# eBox_Power.net
KiCad netlist of a schematic drawn in Altium Designer
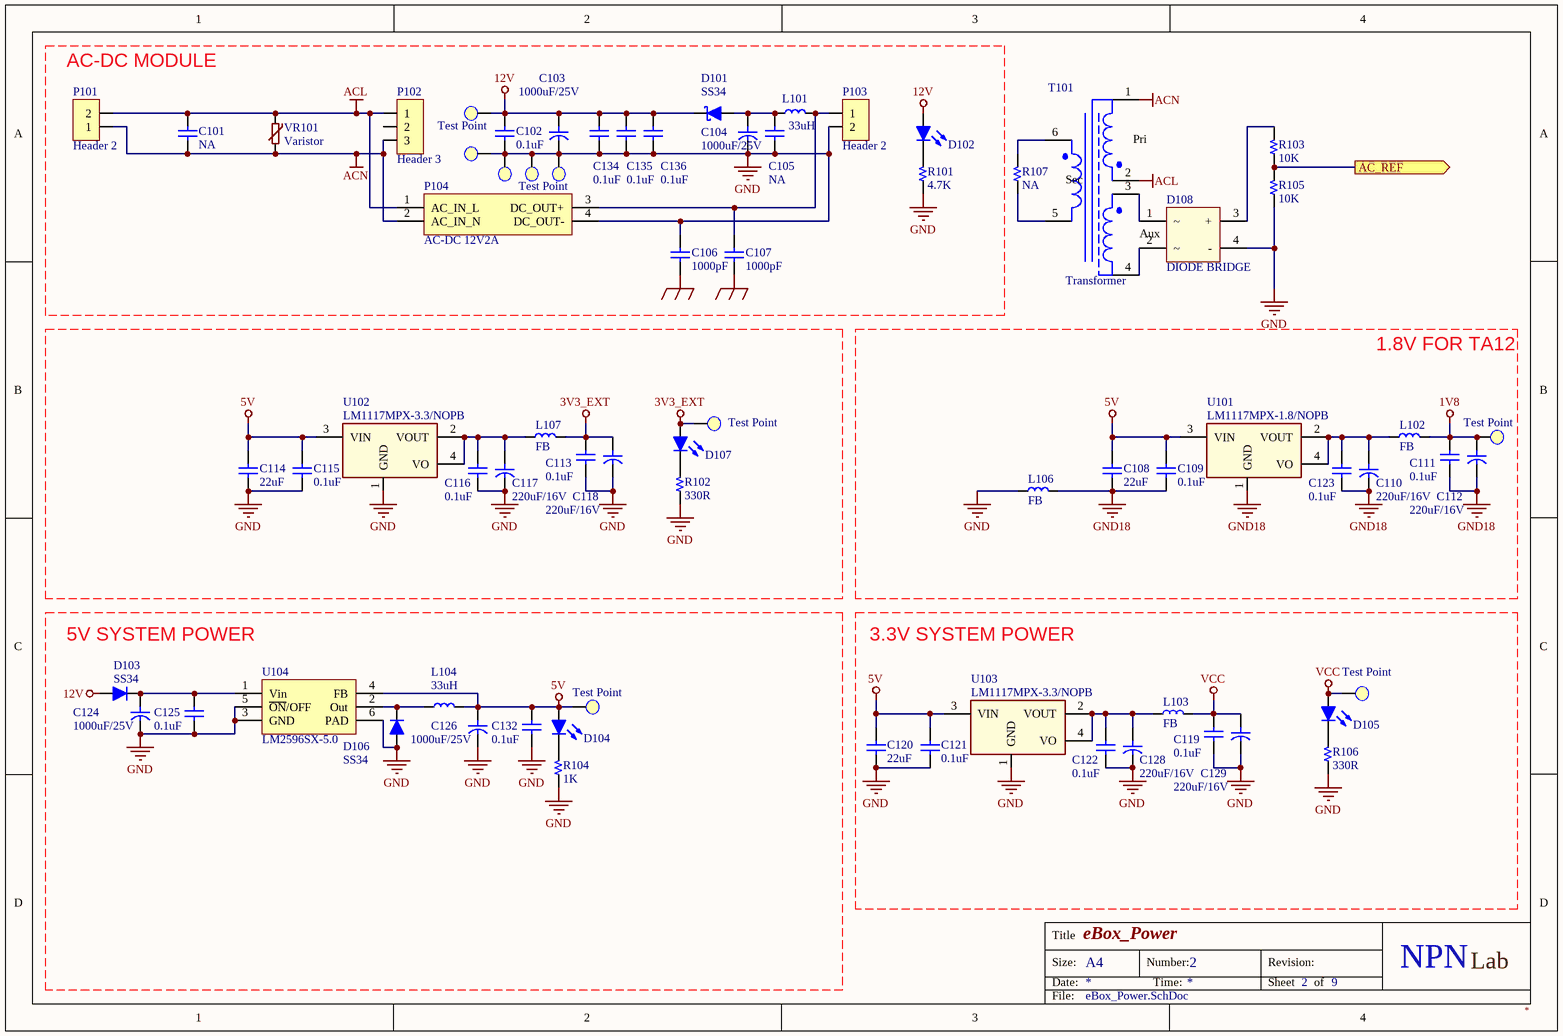
[diagram p0: eBox_Power.SchDoc]

(export (version "E")
  (design (tool "Eeschema 10.0.6"))
  (components
    (comp (ref "1V8")
      (value "Test Point")
      (footprint "TestPoint/SMD/1.5mm")
      (libsource (lib "chipfc_altium_libs_extras") (part "Test Point"))
    )
    (comp (ref "3V3")
      (value "Test Point")
      (footprint "TestPoint/SMD/1.5mm")
      (libsource (lib "chipfc_altium_libs_extras") (part "Test Point"))
    )
    (comp (ref "5V")
      (value "Test Point")
      (footprint "TestPoint/SMD/1.5mm")
      (libsource (lib "chipfc_altium_libs_extras") (part "Test Point"))
    )
    (comp (ref "12V")
      (value "Test Point")
      (footprint "TestPoint/SMD/1.5mm")
      (libsource (lib "chipfc_altium_libs_extras") (part "Test Point"))
    )
    (comp (ref "C101")
      (value "NA")
      (footprint "CAP Ceramic/D7.0/F7.5")
      (description "Capacitor non-pol")
      (libsource (lib "chipfc_altium_libs") (part "Capacitor NP"))
    )
    (comp (ref "C102")
      (value "0.1uF")
      (footprint "C 0805")
      (description "CAP CER 0.1UF 50V X7R 0805")
      (libsource (lib "chipfc_altium_libs") (part "Capacitor NP"))
    )
    (comp (ref "C103")
      (value "1000uF/25V")
      (footprint "CAP/D100/H200/LS50")
      (description "CAP ALUM 1000UF 20% 25V RADIAL")
      (libsource (lib "") (part "Capacitor_1"))
    )
    (comp (ref "C104")
      (value "1000uF/25V")
      (footprint "CAP/D100/H200/LS50")
      (description "CAP ALUM 1000UF 20% 25V RADIAL")
      (libsource (lib "") (part "Capacitor_1"))
    )
    (comp (ref "C105")
      (value "NA")
      (footprint "C 0805")
      (description "CAP SMD 0805")
      (libsource (lib "chipfc_altium_libs") (part "Capacitor NP"))
    )
    (comp (ref "C106")
      (value "1000pF")
      (footprint "CAP Ceramic/W300")
      (description "Capacitor non-pol")
      (libsource (lib "chipfc_altium_libs") (part "Capacitor NP"))
    )
    (comp (ref "C107")
      (value "1000pF")
      (footprint "CAP Ceramic/W300")
      (description "Capacitor non-pol")
      (libsource (lib "chipfc_altium_libs") (part "Capacitor NP"))
    )
    (comp (ref "C108")
      (value "22uF")
      (footprint "C 1210")
      (description "CAP CER 22UF 50V X7R 1210")
      (libsource (lib "chipfc_altium_libs") (part "Capacitor NP"))
    )
    (comp (ref "C109")
      (value "0.1uF")
      (footprint "C 0805")
      (description "CAP CER 0.1UF 50V X7R 0805")
      (libsource (lib "chipfc_altium_libs") (part "Capacitor NP"))
    )
    (comp (ref "C110")
      (value "220uF/16V")
      (footprint "CYL/D.250/LS.100")
      (description "CAP ALUM 220UF 20% 16V RADIAL")
      (libsource (lib "chipfc_altium_libs") (part "Capacitor"))
    )
    (comp (ref "C111")
      (value "0.1uF")
      (footprint "C 0805")
      (description "CAP CER 0.1UF 50V X7R 0805")
      (libsource (lib "chipfc_altium_libs") (part "Capacitor NP"))
    )
    (comp (ref "C112")
      (value "220uF/16V")
      (footprint "CYL/D.250/LS.100")
      (description "CAP ALUM 220UF 20% 16V RADIAL")
      (libsource (lib "chipfc_altium_libs") (part "Capacitor"))
    )
    (comp (ref "C113")
      (value "0.1uF")
      (footprint "C 0805")
      (description "CAP CER 0.1UF 50V X7R 0805")
      (libsource (lib "chipfc_altium_libs") (part "Capacitor NP"))
    )
    (comp (ref "C114")
      (value "22uF")
      (footprint "C 1210")
      (description "CAP CER 22UF 50V X7R 1210")
      (libsource (lib "chipfc_altium_libs") (part "Capacitor NP"))
    )
    (comp (ref "C115")
      (value "0.1uF")
      (footprint "C 0805")
      (description "CAP CER 0.1UF 50V X7R 0805")
      (libsource (lib "chipfc_altium_libs") (part "Capacitor NP"))
    )
    (comp (ref "C116")
      (value "0.1uF")
      (footprint "C 0805")
      (description "CAP CER 0.1UF 50V X7R 0805")
      (libsource (lib "chipfc_altium_libs") (part "Capacitor NP"))
    )
    (comp (ref "C117")
      (value "220uF/16V")
      (footprint "CYL/D.250/LS.100")
      (description "CAP ALUM 220UF 20% 16V RADIAL")
      (libsource (lib "chipfc_altium_libs") (part "Capacitor"))
    )
    (comp (ref "C118")
      (value "220uF/16V")
      (footprint "CYL/D.250/LS.100")
      (description "CAP ALUM 220UF 20% 16V RADIAL")
      (libsource (lib "chipfc_altium_libs") (part "Capacitor"))
    )
    (comp (ref "C119")
      (value "0.1uF")
      (footprint "C 0805")
      (description "CAP CER 0.1UF 50V X7R 0805")
      (libsource (lib "chipfc_altium_libs") (part "Capacitor NP"))
    )
    (comp (ref "C120")
      (value "22uF")
      (footprint "C 1210")
      (description "CAP CER 22UF 50V X7R 1210")
      (libsource (lib "chipfc_altium_libs") (part "Capacitor NP"))
    )
    (comp (ref "C121")
      (value "0.1uF")
      (footprint "C 0805")
      (description "CAP CER 0.1UF 50V X7R 0805")
      (libsource (lib "chipfc_altium_libs") (part "Capacitor NP"))
    )
    (comp (ref "C122")
      (value "0.1uF")
      (footprint "C 0805")
      (description "CAP CER 0.1UF 50V X7R 0805")
      (libsource (lib "chipfc_altium_libs") (part "Capacitor NP"))
    )
    (comp (ref "C123")
      (value "0.1uF")
      (footprint "C 0805")
      (description "CAP CER 0.1UF 50V X7R 0805")
      (libsource (lib "chipfc_altium_libs") (part "Capacitor NP"))
    )
    (comp (ref "C124")
      (value "1000uF/25V")
      (footprint "CAP/D100/H200/LS50")
      (description "CAP ALUM 1000UF 20% 25V RADIAL")
      (libsource (lib "") (part "Capacitor_1"))
    )
    (comp (ref "C125")
      (value "0.1uF")
      (footprint "C 0805")
      (description "CAP CER 0.1UF 50V X7R 0805")
      (libsource (lib "chipfc_altium_libs") (part "Capacitor NP"))
    )
    (comp (ref "C126")
      (value "1000uF/25V")
      (footprint "CAP/D100/H200/LS50")
      (description "CAP ALUM 1000UF 20% 25V RADIAL")
      (libsource (lib "") (part "Capacitor_1"))
    )
    (comp (ref "C128")
      (value "220uF/16V")
      (footprint "CYL/D.250/LS.100")
      (description "CAP ALUM 220UF 20% 16V RADIAL")
      (libsource (lib "chipfc_altium_libs") (part "Capacitor"))
    )
    (comp (ref "C129")
      (value "220uF/16V")
      (footprint "CYL/D.250/LS.100")
      (description "CAP ALUM 220UF 20% 16V RADIAL")
      (libsource (lib "chipfc_altium_libs") (part "Capacitor"))
    )
    (comp (ref "C132")
      (value "0.1uF")
      (footprint "C 0805")
      (description "CAP CER 0.1UF 50V X7R 0805")
      (libsource (lib "chipfc_altium_libs") (part "Capacitor NP"))
    )
    (comp (ref "C134")
      (value "0.1uF")
      (footprint "C 0805")
      (description "CAP CER 0.1UF 50V X7R 0805")
      (libsource (lib "chipfc_altium_libs") (part "Capacitor NP"))
    )
    (comp (ref "C135")
      (value "0.1uF")
      (footprint "C 0805")
      (description "CAP CER 0.1UF 50V X7R 0805")
      (libsource (lib "chipfc_altium_libs") (part "Capacitor NP"))
    )
    (comp (ref "C136")
      (value "0.1uF")
      (footprint "C 0805")
      (description "CAP CER 0.1UF 50V X7R 0805")
      (libsource (lib "chipfc_altium_libs") (part "Capacitor NP"))
    )
    (comp (ref "D101")
      (value "SS34")
      (footprint "DO-214AB (SMC)")
      (description "DIODE SCHOTTKY 40V 3A SUB SMA")
      (libsource (lib "chipfc_altium_libs") (part "Diode Schottky"))
    )
    (comp (ref "D102")
      (value "LED RED 3MM")
      (footprint "LED 3MM - red")
      (description "LED RED CLEAR 0603 SMD")
      (libsource (lib "chipfc_altium_libs") (part "Led"))
    )
    (comp (ref "D103")
      (value "SS34")
      (footprint "DO-214AC (SMA) L")
      (description "DIODE SCHOTTKY 40V 3A SUB SMA")
      (libsource (lib "chipfc_altium_libs") (part "Diode"))
    )
    (comp (ref "D104")
      (value "LED RED 3MM")
      (footprint "LED 3MM - red")
      (description "LED RED CLEAR 0603 SMD")
      (libsource (lib "chipfc_altium_libs") (part "Led"))
    )
    (comp (ref "D105")
      (value "LED RED 3MM")
      (footprint "LED 3MM - red")
      (description "LED RED CLEAR 0603 SMD")
      (libsource (lib "chipfc_altium_libs") (part "Led"))
    )
    (comp (ref "D106")
      (value "SS34")
      (footprint "DO-214AC (SMA) L")
      (description "DIODE SCHOTTKY 40V 3A SUB SMA")
      (libsource (lib "chipfc_altium_libs") (part "Diode"))
    )
    (comp (ref "D107")
      (value "LED RED 3MM")
      (footprint "LED 3MM - red")
      (description "LED RED CLEAR 0603 SMD")
      (libsource (lib "chipfc_altium_libs") (part "Led"))
    )
    (comp (ref "D108")
      (value "DIODE BRIDGE")
      (footprint "DiodeBridge-SOIC4")
      (description "BRIDGE RECT 1P 600V 500MA 4SOIC")
      (libsource (lib "chipfc_altium_libs") (part "DIODE BRIDGE"))
    )
    (comp (ref "GND1")
      (value "Test Point")
      (footprint "TESTPOINT/1/Black")
      (libsource (lib "chipfc_altium_libs_extras") (part "Test Point"))
    )
    (comp (ref "GND2")
      (value "Test Point")
      (footprint "TESTPOINT/1/Black")
      (libsource (lib "chipfc_altium_libs_extras") (part "Test Point"))
    )
    (comp (ref "GND3")
      (value "Test Point")
      (footprint "TESTPOINT/1/Black")
      (libsource (lib "chipfc_altium_libs_extras") (part "Test Point"))
    )
    (comp (ref "GND4")
      (value "Test Point")
      (footprint "TESTPOINT/1/Black")
      (libsource (lib "chipfc_altium_libs_extras") (part "Test Point"))
    )
    (comp (ref "L101")
      (value "33uH")
      (footprint "Inductor SMD 6.5x6.5x3.0")
      (description "FIXED IND 33UH 3A 105 MOHM SMD")
      (fields (field (name "PART NO") "MHCI06030-2R2M-R8"))
      (libsource (lib "chipfc_altium_libs") (part "Inductor"))
    )
    (comp (ref "L102")
      (value "FB")
      (footprint "L 0805 (2012)")
      (description "Chip Ferrite Bead")
      (libsource (lib "chipfc_altium_libs") (part "Inductor"))
    )
    (comp (ref "L103")
      (value "FB")
      (footprint "L 0805 (2012)")
      (description "Chip Ferrite Bead")
      (libsource (lib "chipfc_altium_libs") (part "Inductor"))
    )
    (comp (ref "L104")
      (value "33uH")
      (footprint "Inductor SMD 12x12x8")
      (description "FIXED IND 33UH 3A 64.8 MOHM SMD")
      (libsource (lib "chipfc_altium_libs") (part "Inductor"))
    )
    (comp (ref "L105")
      (value "33uH")
      (footprint "Inductor SMD 12x12x8")
      (description "FIXED IND 33UH 3A 64.8 MOHM SMD")
      (libsource (lib "chipfc_altium_libs") (part "Inductor"))
    )
    (comp (ref "L106")
      (value "FB")
      (footprint "L 0805 (2012)")
      (description "Chip Ferrite Bead")
      (libsource (lib "chipfc_altium_libs") (part "Inductor"))
    )
    (comp (ref "L107")
      (value "FB")
      (footprint "L 0805 (2012)")
      (description "Chip Ferrite Bead")
      (libsource (lib "chipfc_altium_libs") (part "Inductor"))
    )
    (comp (ref "P101")
      (value "Header 2")
      (footprint "HDR/Terminal/2/10mm")
      (description "Header, 2-Pin")
      (libsource (lib "chipfc_altium_libs") (part "Header 2"))
    )
    (comp (ref "P102")
      (value "Header 3")
      (footprint "HDR/Header/3/VH")
      (description "Header, 3-Pin")
      (libsource (lib "chipfc_altium_libs") (part "Header 3"))
    )
    (comp (ref "P103")
      (value "Header 2")
      (footprint "HDR/Header/2/VH")
      (description "Header, 2-Pin")
      (libsource (lib "") (part "Header 2_1"))
    )
    (comp (ref "P104")
      (value "AC-DC 12V2A")
      (footprint "AC-DC 12V2A")
      (description "AC-DC 12V2A MODULE")
      (libsource (lib "chipfc_altium_libs") (part "AC-DC 12V3A"))
    )
    (comp (ref "R101")
      (value "4.7K")
      (footprint "R 0603")
      (description "RES SMD 4.7K OHM 1% 1/10W 0603")
      (libsource (lib "chipfc_altium_libs") (part "Resistor"))
    )
    (comp (ref "R102")
      (value "330R")
      (footprint "R 0603")
      (description "RES SMD 330 OHM 1% 1/10W 0603")
      (libsource (lib "chipfc_altium_libs") (part "Resistor"))
    )
    (comp (ref "R103")
      (value "10K")
      (footprint "R 0805")
      (description "RES SMD 10K OHM 1% 1/10W 0603")
      (libsource (lib "chipfc_altium_libs") (part "Resistor"))
    )
    (comp (ref "R104")
      (value "1K")
      (footprint "R 0603")
      (description "RES SMD 1K OHM 1% 1/10W 0603")
      (libsource (lib "chipfc_altium_libs") (part "Resistor"))
    )
    (comp (ref "R105")
      (value "10K")
      (footprint "R 0805")
      (description "RES SMD 10K OHM 1% 1/10W 0603")
      (libsource (lib "chipfc_altium_libs") (part "Resistor"))
    )
    (comp (ref "R106")
      (value "330R")
      (footprint "R 0603")
      (description "RES SMD 330 OHM 1% 1/10W 0603")
      (libsource (lib "chipfc_altium_libs") (part "Resistor"))
    )
    (comp (ref "R107")
      (value "NA")
      (footprint "R 0805")
      (description "RES SMD 0805")
      (libsource (lib "chipfc_altium_libs") (part "Resistor"))
    )
    (comp (ref "T101")
      (value "Transformer")
      (footprint "Trans. EE10/6P/F")
      (description "Transformer 6-PIN")
      (libsource (lib "chipfc_altium_libs") (part "Trans 6-PIN"))
    )
    (comp (ref "U101")
      (value "LM1117MPX-1.8/NOPB")
      (footprint "SOT-223")
      (description "IC REG LINEAR 1.8V 800MA SOT223")
      (libsource (lib "chipfc_altium_libs") (part "AMS1117"))
    )
    (comp (ref "U102")
      (value "LM1117MPX-3.3/NOPB")
      (footprint "SOT-223")
      (description "IC REG LINEAR 3.3V 800MA SOT223")
      (libsource (lib "chipfc_altium_libs") (part "AMS1117"))
    )
    (comp (ref "U103")
      (value "LM1117MPX-3.3/NOPB")
      (footprint "SOT-223")
      (description "IC REG LINEAR 3.3V 800MA SOT223")
      (libsource (lib "chipfc_altium_libs") (part "AMS1117"))
    )
    (comp (ref "U104")
      (value "LM2596SX-5.0")
      (footprint "TO-263-6")
      (description "IC REG BUCK 5V 3A TO263-5")
      (fields (field (name "PART NO") "LM2576SX-5.0/NOPB"))
      (libsource (lib "chipfc_altium_libs") (part "LM2576SX-5.0"))
    )
    (comp (ref "VCC")
      (value "Test Point")
      (footprint "TestPoint/SMD/1.5mm")
      (libsource (lib "chipfc_altium_libs_extras") (part "Test Point"))
    )
    (comp (ref "VR101")
      (value "Varistor")
      (footprint "VARISTOR DISC 5MM/7MM")
      (libsource (lib "chipfc_altium_libs") (part "Varistor"))
    )
  )
  (nets
    (net (code "1") (name "/AC_REF") (class "Default")
      (node (ref "R103") (pin "1") (pinfunction "1_1") (pintype "passive"))
      (node (ref "R105") (pin "2") (pinfunction "2_2") (pintype "passive"))
    )
    (net (code "2") (name "1V8") (class "Default")
      (node (ref "1V8") (pin "1") (pinfunction "TP_1") (pintype "passive"))
      (node (ref "C111") (pin "1") (pinfunction "1_1") (pintype "passive"))
      (node (ref "C112") (pin "1") (pinfunction "1_1") (pintype "passive"))
      (node (ref "L102") (pin "2") (pinfunction "2_2") (pintype "passive"))
    )
    (net (code "3") (name "3V3_EXT") (class "Default")
      (node (ref "3V3") (pin "1") (pinfunction "TP_1") (pintype "passive"))
      (node (ref "C113") (pin "1") (pinfunction "1_1") (pintype "passive"))
      (node (ref "C118") (pin "1") (pinfunction "1_1") (pintype "passive"))
      (node (ref "D107") (pin "1") (pinfunction "A_1") (pintype "passive"))
      (node (ref "L107") (pin "2") (pinfunction "2_2") (pintype "passive"))
    )
    (net (code "4") (name "5V") (class "Default")
      (node (ref "5V") (pin "1") (pinfunction "TP_1") (pintype "passive"))
      (node (ref "C108") (pin "1") (pinfunction "1_1") (pintype "passive"))
      (node (ref "C109") (pin "1") (pinfunction "1_1") (pintype "passive"))
      (node (ref "C114") (pin "1") (pinfunction "1_1") (pintype "passive"))
      (node (ref "C115") (pin "1") (pinfunction "1_1") (pintype "passive"))
      (node (ref "C120") (pin "1") (pinfunction "1_1") (pintype "passive"))
      (node (ref "C121") (pin "1") (pinfunction "1_1") (pintype "passive"))
      (node (ref "C126") (pin "1") (pinfunction "1_1") (pintype "passive"))
      (node (ref "C132") (pin "1") (pinfunction "1_1") (pintype "passive"))
      (node (ref "D104") (pin "1") (pinfunction "A_1") (pintype "passive"))
      (node (ref "L104") (pin "2") (pinfunction "2_2") (pintype "passive"))
      (node (ref "U101") (pin "3") (pinfunction "VIN_3") (pintype "power_in"))
      (node (ref "U102") (pin "3") (pinfunction "VIN_3") (pintype "power_in"))
      (node (ref "U103") (pin "3") (pinfunction "VIN_3") (pintype "power_in"))
      (node (ref "U104") (pin "4") (pinfunction "FB_4") (pintype "passive"))
    )
    (net (code "5") (name "12V") (class "Default")
      (node (ref "12V") (pin "1") (pinfunction "TP_1") (pintype "passive"))
      (node (ref "C102") (pin "1") (pinfunction "1_1") (pintype "passive"))
      (node (ref "C103") (pin "1") (pinfunction "1_1") (pintype "passive"))
      (node (ref "C134") (pin "1") (pinfunction "1_1") (pintype "passive"))
      (node (ref "C135") (pin "1") (pinfunction "1_1") (pintype "passive"))
      (node (ref "C136") (pin "1") (pinfunction "1_1") (pintype "passive"))
      (node (ref "D101") (pin "2") (pinfunction "K_2") (pintype "passive"))
      (node (ref "D102") (pin "1") (pinfunction "A_1") (pintype "passive"))
      (node (ref "D103") (pin "1") (pinfunction "A_1") (pintype "passive"))
    )
    (net (code "6") (name "ACL") (class "Default")
      (node (ref "C101") (pin "1") (pinfunction "1_1") (pintype "passive"))
      (node (ref "P101") (pin "2") (pinfunction "2_2") (pintype "passive"))
      (node (ref "P102") (pin "1") (pinfunction "1_1") (pintype "passive"))
      (node (ref "P104") (pin "1") (pinfunction "AC_IN_L_1") (pintype "passive"))
      (node (ref "T101") (pin "2") (pinfunction "A2_2") (pintype "passive"))
      (node (ref "VR101") (pin "2") (pinfunction "2_2") (pintype "passive"))
    )
    (net (code "7") (name "ACN") (class "Default")
      (node (ref "C101") (pin "2") (pinfunction "2_2") (pintype "passive"))
      (node (ref "P101") (pin "1") (pinfunction "1_1") (pintype "passive"))
      (node (ref "P102") (pin "3") (pinfunction "3_3") (pintype "passive"))
      (node (ref "P104") (pin "2") (pinfunction "AC_IN_N_2") (pintype "passive"))
      (node (ref "T101") (pin "1") (pinfunction "A1_1") (pintype "passive"))
      (node (ref "VR101") (pin "1") (pinfunction "1_1") (pintype "passive"))
    )
    (net (code "8") (name "GND") (class "Default")
      (node (ref "C102") (pin "2") (pinfunction "2_2") (pintype "passive"))
      (node (ref "C103") (pin "2") (pinfunction "2_2") (pintype "passive"))
      (node (ref "C104") (pin "2") (pinfunction "2_2") (pintype "passive"))
      (node (ref "C105") (pin "2") (pinfunction "2_2") (pintype "passive"))
      (node (ref "C106") (pin "1") (pinfunction "1_1") (pintype "passive"))
      (node (ref "C113") (pin "2") (pinfunction "2_2") (pintype "passive"))
      (node (ref "C114") (pin "2") (pinfunction "2_2") (pintype "passive"))
      (node (ref "C115") (pin "2") (pinfunction "2_2") (pintype "passive"))
      (node (ref "C116") (pin "2") (pinfunction "2_2") (pintype "passive"))
      (node (ref "C117") (pin "2") (pinfunction "2_2") (pintype "passive"))
      (node (ref "C118") (pin "2") (pinfunction "2_2") (pintype "passive"))
      (node (ref "C119") (pin "2") (pinfunction "2_2") (pintype "passive"))
      (node (ref "C120") (pin "2") (pinfunction "2_2") (pintype "passive"))
      (node (ref "C121") (pin "2") (pinfunction "2_2") (pintype "passive"))
      (node (ref "C122") (pin "2") (pinfunction "2_2") (pintype "passive"))
      (node (ref "C124") (pin "2") (pinfunction "2_2") (pintype "passive"))
      (node (ref "C125") (pin "2") (pinfunction "2_2") (pintype "passive"))
      (node (ref "C126") (pin "2") (pinfunction "2_2") (pintype "passive"))
      (node (ref "C128") (pin "2") (pinfunction "2_2") (pintype "passive"))
      (node (ref "C129") (pin "2") (pinfunction "2_2") (pintype "passive"))
      (node (ref "C132") (pin "2") (pinfunction "2_2") (pintype "passive"))
      (node (ref "C134") (pin "2") (pinfunction "2_2") (pintype "passive"))
      (node (ref "C135") (pin "2") (pinfunction "2_2") (pintype "passive"))
      (node (ref "C136") (pin "2") (pinfunction "2_2") (pintype "passive"))
      (node (ref "D106") (pin "1") (pinfunction "A_1") (pintype "passive"))
      (node (ref "D108") (pin "4") (pinfunction "-_4") (pintype "passive"))
      (node (ref "GND1") (pin "1") (pinfunction "TP_1") (pintype "passive"))
      (node (ref "GND2") (pin "1") (pinfunction "TP_1") (pintype "passive"))
      (node (ref "GND3") (pin "1") (pinfunction "TP_1") (pintype "passive"))
      (node (ref "GND4") (pin "1") (pinfunction "TP_1") (pintype "passive"))
      (node (ref "L106") (pin "1") (pinfunction "1_1") (pintype "passive"))
      (node (ref "P103") (pin "2") (pinfunction "2_2") (pintype "passive"))
      (node (ref "P104") (pin "4") (pinfunction "DC_OUT-_4") (pintype "passive"))
      (node (ref "R101") (pin "1") (pinfunction "1_1") (pintype "passive"))
      (node (ref "R102") (pin "1") (pinfunction "1_1") (pintype "passive"))
      (node (ref "R104") (pin "1") (pinfunction "1_1") (pintype "passive"))
      (node (ref "R105") (pin "1") (pinfunction "1_1") (pintype "passive"))
      (node (ref "R106") (pin "1") (pinfunction "1_1") (pintype "passive"))
      (node (ref "U102") (pin "1") (pinfunction "GND_1") (pintype "passive"))
      (node (ref "U103") (pin "1") (pinfunction "GND_1") (pintype "passive"))
      (node (ref "U104") (pin "3") (pinfunction "GND_3") (pintype "passive"))
      (node (ref "U104") (pin "5") (pinfunction "~{ON}/OFF_5") (pintype "passive"))
      (node (ref "U104") (pin "6") (pinfunction "PAD_6") (pintype "passive"))
    )
    (net (code "9") (name "GND18") (class "Default")
      (node (ref "C108") (pin "2") (pinfunction "2_2") (pintype "passive"))
      (node (ref "C109") (pin "2") (pinfunction "2_2") (pintype "passive"))
      (node (ref "C110") (pin "2") (pinfunction "2_2") (pintype "passive"))
      (node (ref "C111") (pin "2") (pinfunction "2_2") (pintype "passive"))
      (node (ref "C112") (pin "2") (pinfunction "2_2") (pintype "passive"))
      (node (ref "C123") (pin "2") (pinfunction "2_2") (pintype "passive"))
      (node (ref "L106") (pin "2") (pinfunction "2_2") (pintype "passive"))
      (node (ref "U101") (pin "1") (pinfunction "GND_1") (pintype "passive"))
    )
    (net (code "10") (name "GNDEARTH") (class "Default")
      (node (ref "C106") (pin "2") (pinfunction "2_2") (pintype "passive"))
      (node (ref "C107") (pin "2") (pinfunction "2_2") (pintype "passive"))
    )
    (net (code "11") (name "Net-(D101-A)") (class "Default")
      (node (ref "C104") (pin "1") (pinfunction "1_1") (pintype "passive"))
      (node (ref "C105") (pin "1") (pinfunction "1_1") (pintype "passive"))
      (node (ref "D101") (pin "1") (pinfunction "A_1") (pintype "passive"))
      (node (ref "L101") (pin "1") (pinfunction "1_1") (pintype "passive"))
      (node (ref "L105") (pin "1") (pinfunction "1_1") (pintype "passive"))
    )
    (net (code "12") (name "Net-(D102-K)") (class "Default")
      (node (ref "D102") (pin "2") (pinfunction "K_2") (pintype "passive"))
      (node (ref "R101") (pin "2") (pinfunction "2_2") (pintype "passive"))
    )
    (net (code "13") (name "Net-(D103-K)") (class "Default")
      (node (ref "C124") (pin "1") (pinfunction "1_1") (pintype "passive"))
      (node (ref "C125") (pin "1") (pinfunction "1_1") (pintype "passive"))
      (node (ref "D103") (pin "2") (pinfunction "K_2") (pintype "passive"))
      (node (ref "U104") (pin "1") (pinfunction "Vin_1") (pintype "passive"))
    )
    (net (code "14") (name "Net-(D104-K)") (class "Default")
      (node (ref "D104") (pin "2") (pinfunction "K_2") (pintype "passive"))
      (node (ref "R104") (pin "2") (pinfunction "2_2") (pintype "passive"))
    )
    (net (code "15") (name "Net-(D105-K)") (class "Default")
      (node (ref "D105") (pin "2") (pinfunction "K_2") (pintype "passive"))
      (node (ref "R106") (pin "2") (pinfunction "2_2") (pintype "passive"))
    )
    (net (code "16") (name "Net-(D106-K)") (class "Default")
      (node (ref "D106") (pin "2") (pinfunction "K_2") (pintype "passive"))
      (node (ref "L104") (pin "1") (pinfunction "1_1") (pintype "passive"))
      (node (ref "U104") (pin "2") (pinfunction "Out_2") (pintype "passive"))
    )
    (net (code "17") (name "Net-(D107-K)") (class "Default")
      (node (ref "D107") (pin "2") (pinfunction "K_2") (pintype "passive"))
      (node (ref "R102") (pin "2") (pinfunction "2_2") (pintype "passive"))
    )
    (net (code "18") (name "Net-(D108-+)") (class "Default")
      (node (ref "D108") (pin "3") (pinfunction "+_3") (pintype "passive"))
      (node (ref "R103") (pin "2") (pinfunction "2_2") (pintype "passive"))
    )
    (net (code "19") (name "Net-(P104-DC_OUT+)") (class "Default")
      (node (ref "C107") (pin "1") (pinfunction "1_1") (pintype "passive"))
      (node (ref "L101") (pin "2") (pinfunction "2_2") (pintype "passive"))
      (node (ref "L105") (pin "2") (pinfunction "2_2") (pintype "passive"))
      (node (ref "P103") (pin "1") (pinfunction "1_1") (pintype "passive"))
      (node (ref "P104") (pin "3") (pinfunction "DC_OUT+_3") (pintype "passive"))
    )
    (net (code "20") (name "Net-(T101-B1)") (class "Default")
      (node (ref "D108") (pin "1") (pinfunction "~_1") (pintype "passive"))
      (node (ref "T101") (pin "3") (pinfunction "B1_3") (pintype "passive"))
    )
    (net (code "21") (name "Net-(T101-B2)") (class "Default")
      (node (ref "D108") (pin "2") (pinfunction "~_2") (pintype "passive"))
      (node (ref "T101") (pin "4") (pinfunction "B2_4") (pintype "passive"))
    )
    (net (code "22") (name "Net-(T101-C1)") (class "Default")
      (node (ref "R107") (pin "2") (pinfunction "2_2") (pintype "passive"))
      (node (ref "T101") (pin "6") (pinfunction "C1_6") (pintype "passive"))
    )
    (net (code "23") (name "Net-(T101-C2)") (class "Default")
      (node (ref "R107") (pin "1") (pinfunction "1_1") (pintype "passive"))
      (node (ref "T101") (pin "5") (pinfunction "C2_5") (pintype "passive"))
    )
    (net (code "24") (name "Net-(U101-VO)") (class "Default")
      (node (ref "C110") (pin "1") (pinfunction "1_1") (pintype "passive"))
      (node (ref "C123") (pin "1") (pinfunction "1_1") (pintype "passive"))
      (node (ref "L102") (pin "1") (pinfunction "1_1") (pintype "passive"))
      (node (ref "U101") (pin "2") (pinfunction "VOUT_2") (pintype "passive"))
      (node (ref "U101") (pin "4") (pinfunction "VO_4") (pintype "passive"))
    )
    (net (code "25") (name "Net-(U102-VO)") (class "Default")
      (node (ref "C116") (pin "1") (pinfunction "1_1") (pintype "passive"))
      (node (ref "C117") (pin "1") (pinfunction "1_1") (pintype "passive"))
      (node (ref "L107") (pin "1") (pinfunction "1_1") (pintype "passive"))
      (node (ref "U102") (pin "2") (pinfunction "VOUT_2") (pintype "passive"))
      (node (ref "U102") (pin "4") (pinfunction "VO_4") (pintype "passive"))
    )
    (net (code "26") (name "Net-(U103-VO)") (class "Default")
      (node (ref "C122") (pin "1") (pinfunction "1_1") (pintype "passive"))
      (node (ref "C128") (pin "1") (pinfunction "1_1") (pintype "passive"))
      (node (ref "L103") (pin "1") (pinfunction "1_1") (pintype "passive"))
      (node (ref "U103") (pin "2") (pinfunction "VOUT_2") (pintype "passive"))
      (node (ref "U103") (pin "4") (pinfunction "VO_4") (pintype "passive"))
    )
    (net (code "27") (name "VCC") (class "Default")
      (node (ref "C119") (pin "1") (pinfunction "1_1") (pintype "passive"))
      (node (ref "C129") (pin "1") (pinfunction "1_1") (pintype "passive"))
      (node (ref "D105") (pin "1") (pinfunction "A_1") (pintype "passive"))
      (node (ref "L103") (pin "2") (pinfunction "2_2") (pintype "passive"))
      (node (ref "VCC") (pin "1") (pinfunction "TP_1") (pintype "passive"))
    )
    (net (code "28") (name "unconnected-(P102-Pad2)") (class "Default")
      (node (ref "P102") (pin "2") (pinfunction "2_2") (pintype "passive"))
    )
  )
)
